# Schematic.net
KiCad netlist of a schematic drawn in Altium Designer
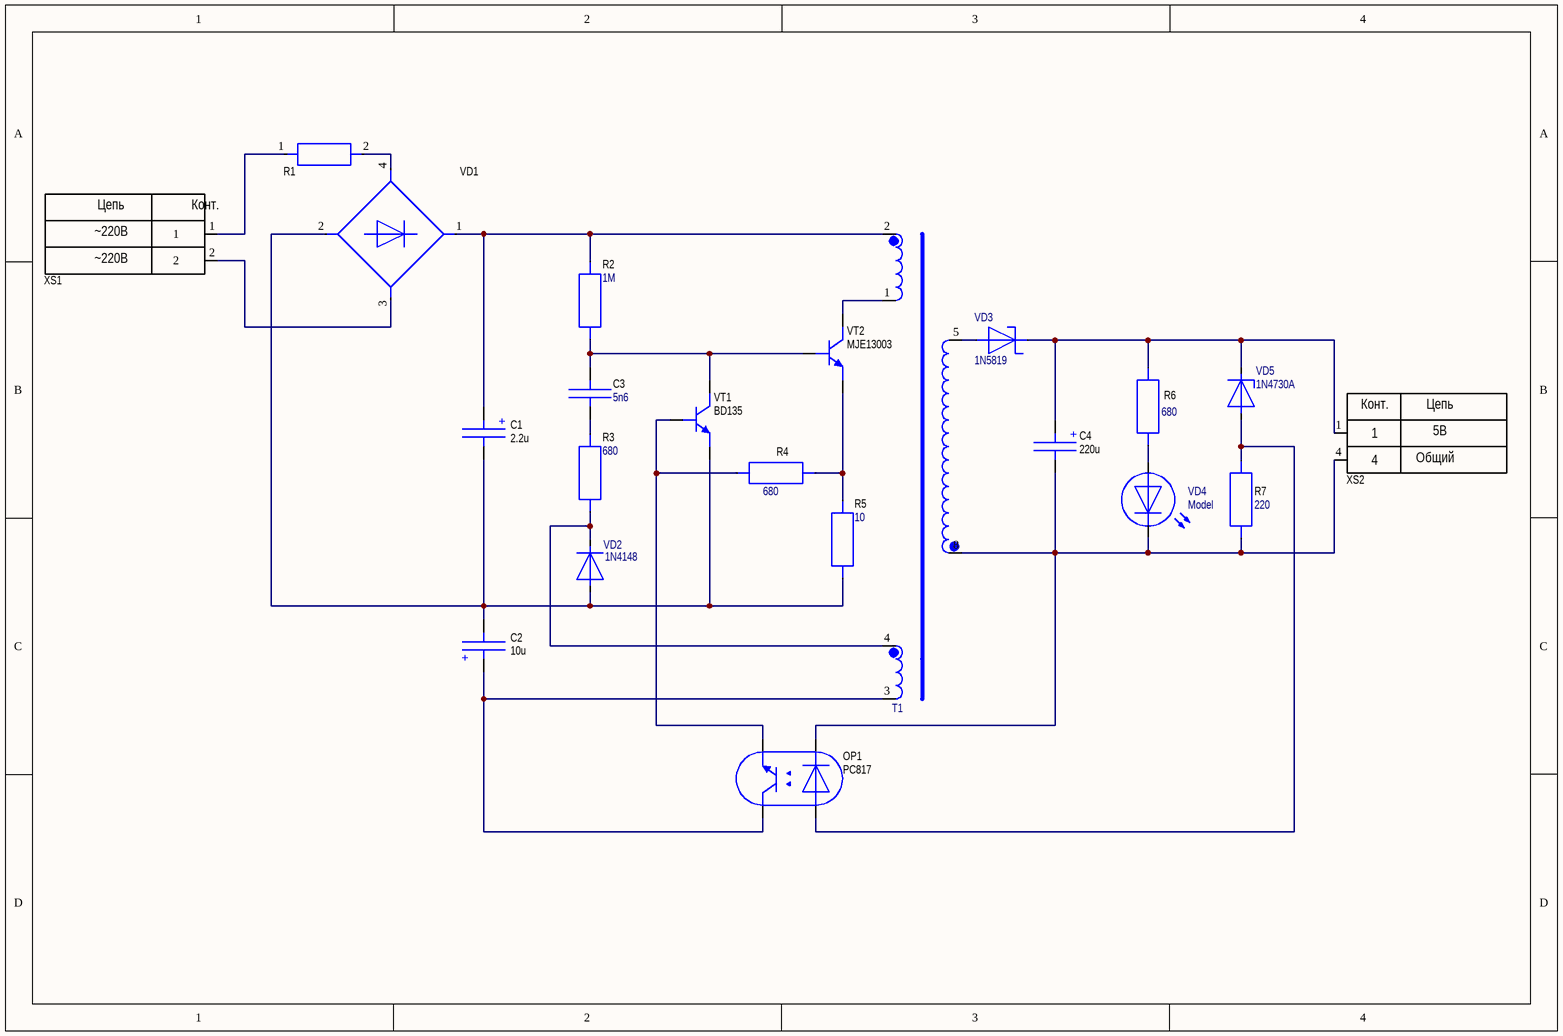
[diagram p0: Schematic.SchDoc]

(export (version "E")
  (design (tool "Eeschema 10.0.6"))
  (components
    (comp (ref "C1")
      (value "2.2u")
      (footprint "ECAP: 10x12")
      (libsource (lib "Devices") (part "ECAP{colon} 2.2u_400v"))
    )
    (comp (ref "C2")
      (value "10u")
      (footprint "ECAP: 10x20")
      (libsource (lib "Devices") (part "ECAP{colon} 10u_400v"))
    )
    (comp (ref "C3") (value "5n6") (footprint "CAP: 3x4") (libsource (lib "Devices") (part "CAP{colon} 56P")))
    (comp (ref "C4")
      (value "220u")
      (footprint "ECAP: 6x11")
      (libsource (lib "Devices") (part "ECAP{colon} 220u_10v"))
    )
    (comp (ref "OP1") (value "PC817") (footprint "DIP-4") (libsource (lib "Devices") (part "PC817")))
    (comp (ref "R1")
      (value "RES 2W_1Ohm")
      (footprint "RES: 0.5W")
      (libsource (lib "Devices") (part "RES 0.5W"))
    )
    (comp (ref "R2") (value "1M") (footprint "RES: 0.25W") (libsource (lib "Devices") (part "RES 0.25W")))
    (comp (ref "R3") (value "680") (footprint "RES: 0.25W") (libsource (lib "Devices") (part "RES 0.25W")))
    (comp (ref "R4") (value "680") (footprint "RES: 0.25W") (libsource (lib "Devices") (part "RES 0.25W")))
    (comp (ref "R5") (value "10") (footprint "RES: 0.25W") (libsource (lib "Devices") (part "RES 0.25W")))
    (comp (ref "R6") (value "680") (footprint "RES: 0.25W") (libsource (lib "Devices") (part "RES 0.25W")))
    (comp (ref "R7") (value "220") (footprint "RES: 0.25W") (libsource (lib "Devices") (part "RES 0.25W")))
    (comp (ref "T1") (value "200x15x7") (footprint "TSD-0816") (libsource (lib "Devices") (part "TRANSFORM")))
    (comp (ref "VD1") (value "DB106") (footprint "DFM") (libsource (lib "Devices") (part "DB106")))
    (comp (ref "VD2") (value "1N4148") (footprint "DO-35") (libsource (lib "Devices") (part "1N4148")))
    (comp (ref "VD3") (value "1N5819") (footprint "DO-41") (libsource (lib "Devices") (part "1N5819")))
    (comp (ref "VD4")
      (value "Model")
      (footprint "LED: RED")
      (libsource (lib "Devices") (part "LED{colon}RED"))
    )
    (comp (ref "VD5") (value "1N4730A") (footprint "DO-41") (libsource (lib "Devices") (part "1N4730A")))
    (comp (ref "VT1")
      (value "BD135")
      (footprint "TO-126 / SOT-32")
      (libsource (lib "Devices") (part "BD135"))
    )
    (comp (ref "VT2")
      (value "MJE13003")
      (footprint "TO-126 / SOT-32")
      (libsource (lib "Devices") (part "MJE13003"))
    )
    (comp (ref "XS1")
      (value "306-021-12")
      (footprint "KLS2-306-021-12 - duplicate")
      (libsource (lib "Devices") (part "306-021-12"))
    )
    (comp (ref "XS2") (value "USB 2.0") (footprint "USB 2.0") (libsource (lib "Devices") (part "USB 2.0")))
  )
  (nets
    (net (code "1") (name "Net-(C2-Pad1)") (class "Default")
      (node (ref "C2") (pin "1") (pinfunction "1_1") (pintype "passive"))
      (node (ref "OP1") (pin "4") (pinfunction "4_4") (pintype "passive"))
      (node (ref "T1") (pin "3") (pinfunction "3_3") (pintype "passive"))
    )
    (net (code "2") (name "Net-(OP1-Anode)") (class "Default")
      (node (ref "OP1") (pin "1") (pinfunction "Anode_1") (pintype "passive"))
      (node (ref "R7") (pin "2") (pinfunction "8_2") (pintype "passive"))
      (node (ref "VD5") (pin "1") (pinfunction "1_1") (pintype "passive"))
    )
    (net (code "3") (name "Net-(OP1-Cathode)") (class "Default")
      (node (ref "C4") (pin "2") (pinfunction "2_2") (pintype "passive"))
      (node (ref "OP1") (pin "2") (pinfunction "Cathode_2") (pintype "passive"))
      (node (ref "R7") (pin "1") (pinfunction "1_1") (pintype "passive"))
      (node (ref "T1") (pin "8") (pinfunction "8_8") (pintype "passive"))
      (node (ref "VD4") (pin "2") (pinfunction "2_2") (pintype "passive"))
      (node (ref "XS2") (pin "4") (pinfunction "4_4") (pintype "passive"))
    )
    (net (code "4") (name "Net-(R1-8)") (class "Default")
      (node (ref "R1") (pin "2") (pinfunction "8_2") (pintype "passive"))
      (node (ref "VD1") (pin "4") (pinfunction "4_4") (pintype "passive"))
    )
    (net (code "5") (name "Net-(R1-Pad1)") (class "Default")
      (node (ref "R1") (pin "1") (pinfunction "1_1") (pintype "passive"))
      (node (ref "XS1") (pin "1") (pinfunction "1_1") (pintype "passive"))
    )
    (net (code "6") (name "Net-(R2-8)") (class "Default")
      (node (ref "C1") (pin "1") (pinfunction "1_1") (pintype "passive"))
      (node (ref "R2") (pin "2") (pinfunction "8_2") (pintype "passive"))
      (node (ref "T1") (pin "2") (pinfunction "2_2") (pintype "passive"))
      (node (ref "VD1") (pin "1") (pinfunction "1_1") (pintype "passive"))
    )
    (net (code "7") (name "Net-(R3-8)") (class "Default")
      (node (ref "C3") (pin "1") (pinfunction "1_1") (pintype "passive"))
      (node (ref "R3") (pin "2") (pinfunction "8_2") (pintype "passive"))
    )
    (net (code "8") (name "Net-(R3-Pad1)") (class "Default")
      (node (ref "R3") (pin "1") (pinfunction "1_1") (pintype "passive"))
      (node (ref "T1") (pin "4") (pinfunction "4_4") (pintype "passive"))
      (node (ref "VD2") (pin "2") (pinfunction "2_2") (pintype "passive"))
    )
    (net (code "9") (name "Net-(R4-8)") (class "Default")
      (node (ref "OP1") (pin "3") (pinfunction "3_3") (pintype "passive"))
      (node (ref "R4") (pin "2") (pinfunction "8_2") (pintype "passive"))
      (node (ref "VT1") (pin "1") (pinfunction "B_1") (pintype "passive"))
    )
    (net (code "10") (name "Net-(R5-8)") (class "Default")
      (node (ref "C1") (pin "2") (pinfunction "2_2") (pintype "passive"))
      (node (ref "C2") (pin "2") (pinfunction "2_2") (pintype "passive"))
      (node (ref "R5") (pin "2") (pinfunction "8_2") (pintype "passive"))
      (node (ref "VD1") (pin "2") (pinfunction "2_2") (pintype "passive"))
      (node (ref "VD2") (pin "1") (pinfunction "1_1") (pintype "passive"))
      (node (ref "VT1") (pin "3") (pinfunction "E_3") (pintype "passive"))
    )
    (net (code "11") (name "Net-(R6-8)") (class "Default")
      (node (ref "C4") (pin "1") (pinfunction "1_1") (pintype "passive"))
      (node (ref "R6") (pin "2") (pinfunction "8_2") (pintype "passive"))
      (node (ref "VD3") (pin "2") (pintype "passive"))
      (node (ref "VD5") (pin "2") (pinfunction "2_2") (pintype "passive"))
      (node (ref "XS2") (pin "1") (pinfunction "1_1") (pintype "passive"))
    )
    (net (code "12") (name "Net-(R6-Pad1)") (class "Default")
      (node (ref "R6") (pin "1") (pinfunction "1_1") (pintype "passive"))
      (node (ref "VD4") (pin "1") (pintype "passive"))
    )
    (net (code "13") (name "Net-(VD1-Pad3)") (class "Default")
      (node (ref "VD1") (pin "3") (pinfunction "3_3") (pintype "passive"))
      (node (ref "XS1") (pin "2") (pinfunction "2_2") (pintype "passive"))
    )
    (net (code "14") (name "Net-(VD3-3)") (class "Default")
      (node (ref "T1") (pin "5") (pinfunction "5_5") (pintype "passive"))
      (node (ref "VD3") (pin "1") (pinfunction "3_1") (pintype "passive"))
    )
    (net (code "15") (name "Net-(VT1-C)") (class "Default")
      (node (ref "C3") (pin "2") (pinfunction "2_2") (pintype "passive"))
      (node (ref "R2") (pin "1") (pinfunction "1_1") (pintype "passive"))
      (node (ref "VT1") (pin "2") (pinfunction "C_2") (pintype "passive"))
      (node (ref "VT2") (pin "1") (pinfunction "B_1") (pintype "passive"))
    )
    (net (code "16") (name "Net-(VT2-C)") (class "Default")
      (node (ref "T1") (pin "1") (pinfunction "1_1") (pintype "passive"))
      (node (ref "VT2") (pin "2") (pinfunction "C_2") (pintype "passive"))
    )
    (net (code "17") (name "Net-(VT2-E)") (class "Default")
      (node (ref "R4") (pin "1") (pinfunction "1_1") (pintype "passive"))
      (node (ref "R5") (pin "1") (pinfunction "1_1") (pintype "passive"))
      (node (ref "VT2") (pin "3") (pinfunction "E_3") (pintype "passive"))
    )
  )
)
